# Ethernet.net
KiCad netlist of a schematic drawn in Altium Designer
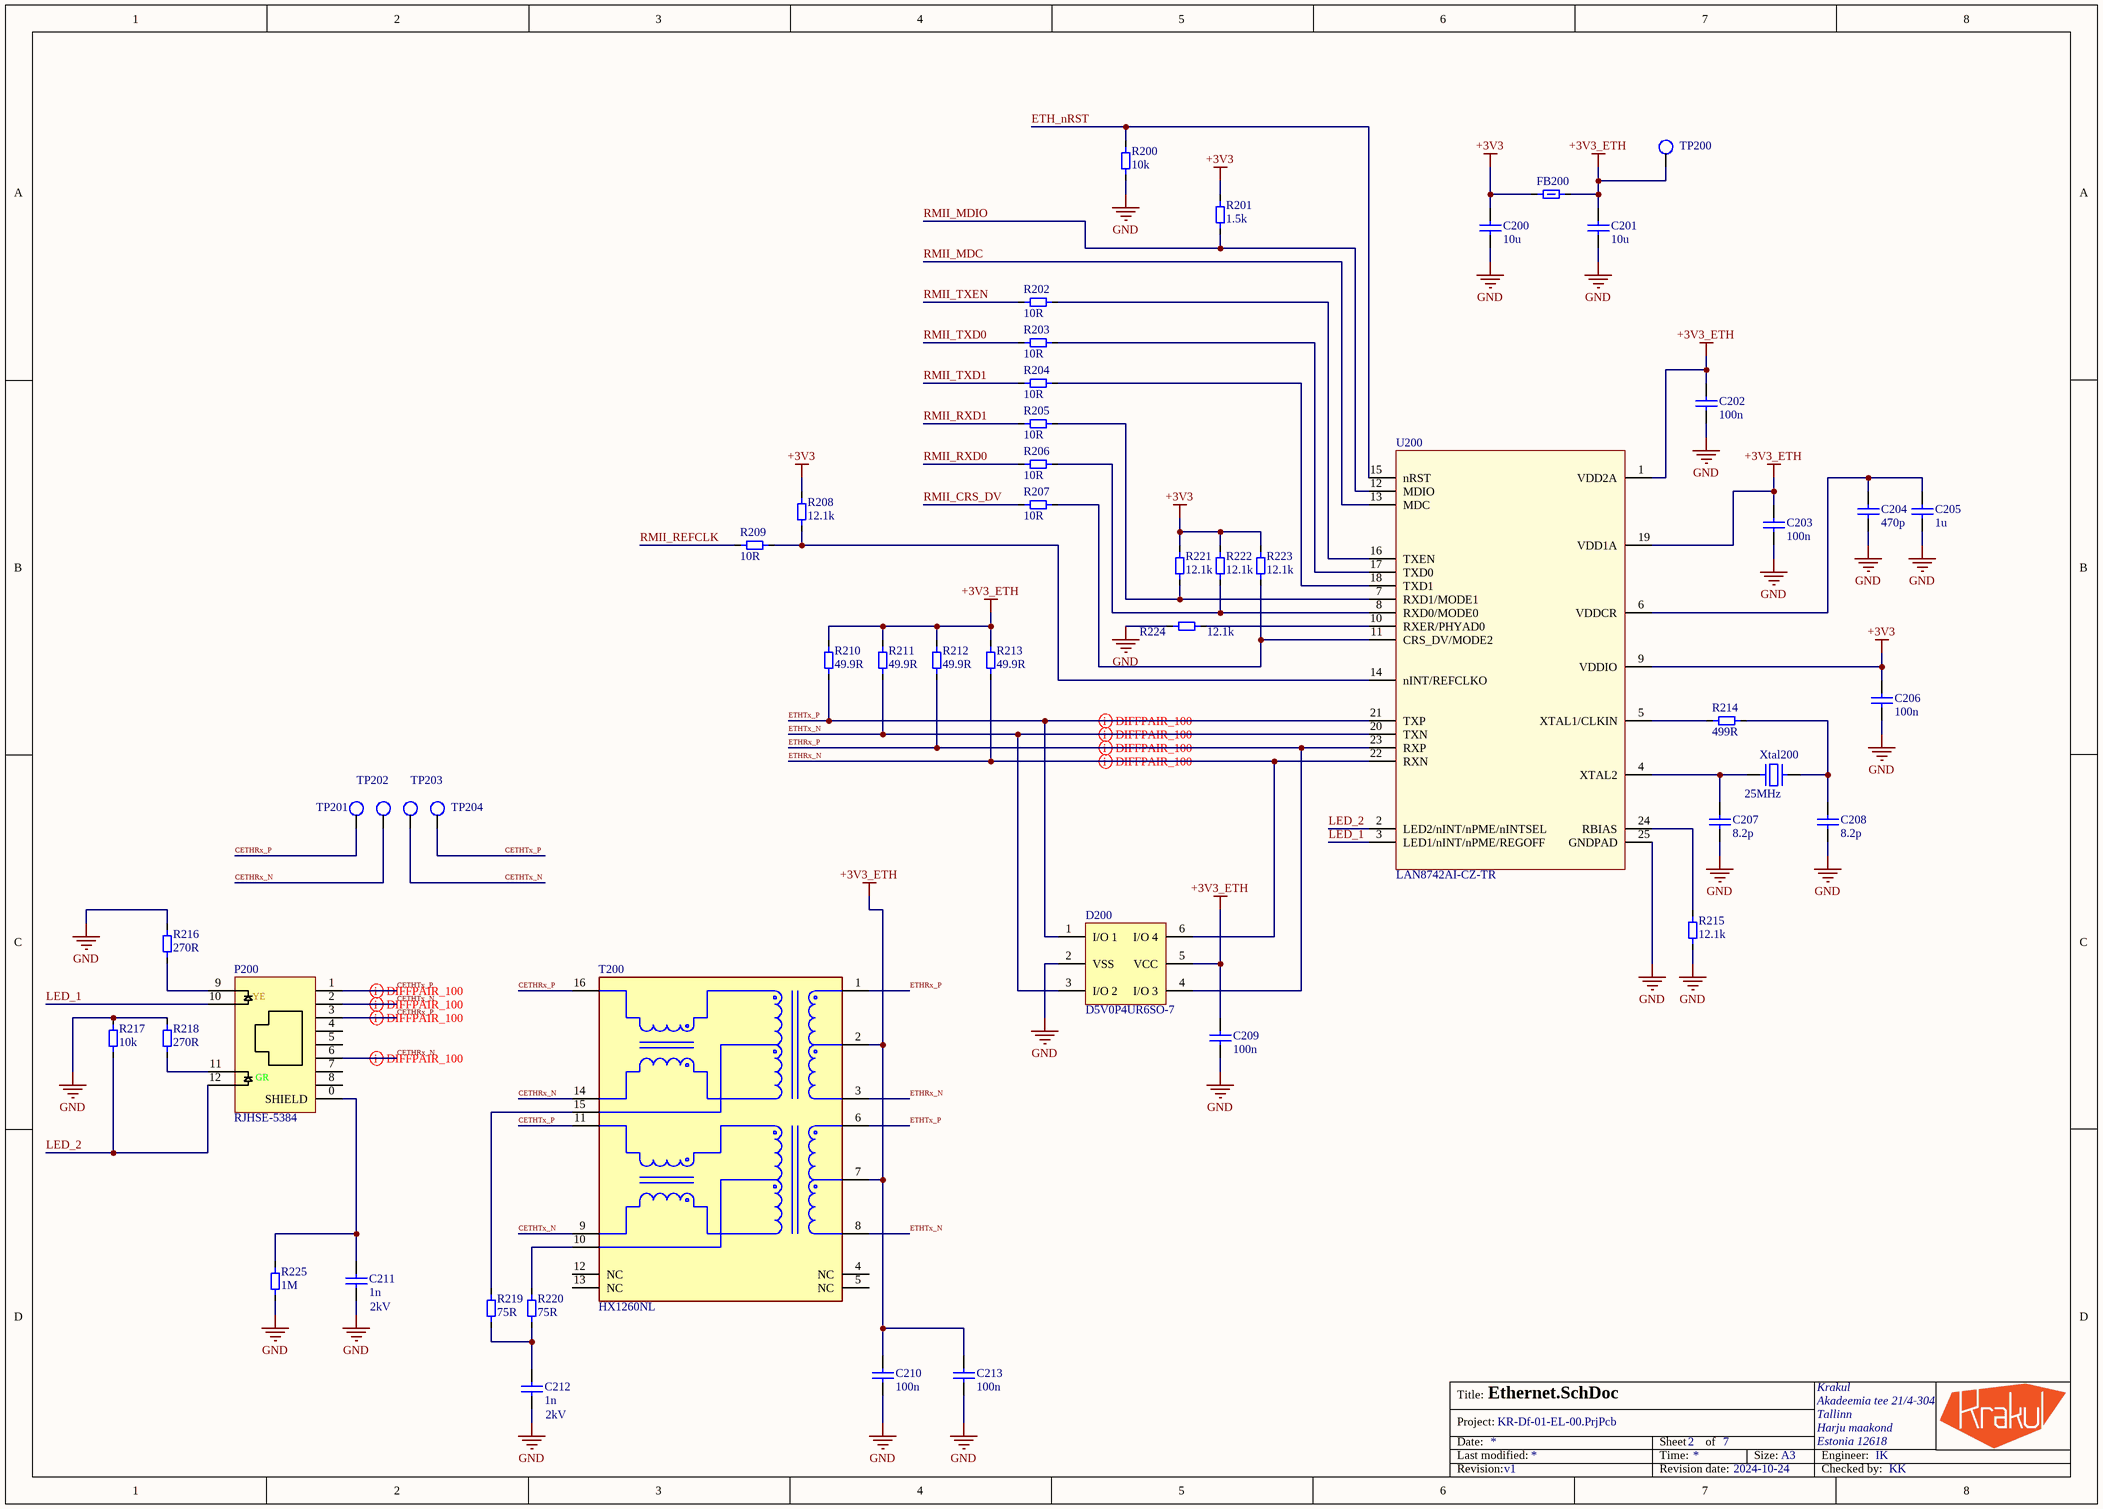
[diagram p0: Ethernet.SchDoc]

(export (version "E")
  (design (tool "Eeschema 10.0.6"))
  (components
    (comp (ref "C200")
      (value "10u")
      (footprint "MLCC_0603_M")
      (description "MLCC, 0603, 10u, 10%, 25V, X5R")
      (fields (field (name "VOLTAGE") "25V") (field (name "MANUFACTURER") "Any"))
      (libsource (lib "Krakul Vault") (part "CAPACITOR_NONPOL_IEC"))
    )
    (comp (ref "C201")
      (value "10u")
      (footprint "MLCC_0603_M")
      (description "MLCC, 0603, 10u, 10%, 25V, X5R")
      (fields (field (name "VOLTAGE") "25V") (field (name "MANUFACTURER") "Any"))
      (libsource (lib "Krakul Vault") (part "CAPACITOR_NONPOL_IEC"))
    )
    (comp (ref "C202")
      (value "100n")
      (footprint "MLCC_0402_M")
      (description "MLCC, 0402, 100n, 10%, 10V, X5R")
      (fields (field (name "TOLERANCE") "10%") (field (name "MANUFACTURER") "Any"))
      (libsource (lib "Krakul Vault") (part "CAPACITOR_NONPOL_IEC"))
    )
    (comp (ref "C203")
      (value "100n")
      (footprint "MLCC_0402_M")
      (description "MLCC, 0402, 100n, 10%, 10V, X5R")
      (fields (field (name "TOLERANCE") "10%") (field (name "MANUFACTURER") "Any"))
      (libsource (lib "Krakul Vault") (part "CAPACITOR_NONPOL_IEC"))
    )
    (comp (ref "C204")
      (value "470p")
      (footprint "MLCC_0402_M")
      (description "MLCC, 0402, 470p, 5%, 50V, C0G/NP0")
      (fields (field (name "MANUFACTURER") "Any") (field (name "TOLERANCE") "5%"))
      (libsource (lib "Krakul Vault") (part "CAPACITOR_NONPOL_IEC"))
    )
    (comp (ref "C205")
      (value "1u")
      (footprint "MLCC_0603_M")
      (description "MLCC, 0603, 1u, 10%, 10V, X7R")
      (fields (field (name "TOLERANCE") "10%") (field (name "MANUFACTURER") "Any"))
      (libsource (lib "Krakul Vault") (part "CAPACITOR_NONPOL_IEC"))
    )
    (comp (ref "C206")
      (value "100n")
      (footprint "MLCC_0402_M")
      (description "MLCC, 0402, 100n, 10%, 10V, X5R")
      (fields (field (name "TOLERANCE") "10%") (field (name "MANUFACTURER") "Any"))
      (libsource (lib "Krakul Vault") (part "CAPACITOR_NONPOL_IEC"))
    )
    (comp (ref "C207")
      (value "8.2p")
      (footprint "MLCC_0402_M")
      (description "MLCC, 0402, 8.2p, 5%, 50V, C0G/NP0")
      (fields (field (name "MANUFACTURER") "Any") (field (name "VOLTAGE") "50V"))
      (libsource (lib "Krakul Vault") (part "CAPACITOR_NONPOL_IEC"))
    )
    (comp (ref "C208")
      (value "8.2p")
      (footprint "MLCC_0402_M")
      (description "MLCC, 0402, 8.2p, 5%, 50V, C0G/NP0")
      (fields (field (name "MANUFACTURER") "Any") (field (name "VOLTAGE") "50V"))
      (libsource (lib "Krakul Vault") (part "CAPACITOR_NONPOL_IEC"))
    )
    (comp (ref "C209")
      (value "100n")
      (footprint "MLCC_0402_M")
      (description "MLCC, 0402, 100n, 10%, 10V, X5R")
      (fields (field (name "TOLERANCE") "10%") (field (name "MANUFACTURER") "Any"))
      (libsource (lib "Krakul Vault") (part "CAPACITOR_NONPOL_IEC"))
    )
    (comp (ref "C210")
      (value "100n")
      (footprint "MLCC_0402_M")
      (description "MLCC, 0402, 100n, 10%, 10V, X5R")
      (fields (field (name "TOLERANCE") "10%") (field (name "MANUFACTURER") "Any"))
      (libsource (lib "Krakul Vault") (part "CAPACITOR_NONPOL_IEC"))
    )
    (comp (ref "C211")
      (value "1n")
      (footprint "MLCC_1206_M")
      (description "MLCC, 1206, 1n, 10%, 2kV, X7R")
      (fields
        (field (name "VOLTAGE RATING (DC)") "2kV")
        (field (name "MANUFACTURER") "Any")
        (field (name "VOLTAGE") "2kV")
      )
      (libsource (lib "Krakul Vault") (part "CAPACITOR_NONPOL_IEC"))
    )
    (comp (ref "C212")
      (value "1n")
      (footprint "MLCC_1206_M")
      (description "MLCC, 1206, 1n, 10%, 2kV, X7R")
      (fields
        (field (name "VOLTAGE RATING (DC)") "2kV")
        (field (name "MANUFACTURER") "Any")
        (field (name "VOLTAGE") "2kV")
      )
      (libsource (lib "Krakul Vault") (part "CAPACITOR_NONPOL_IEC"))
    )
    (comp (ref "C213")
      (value "100n")
      (footprint "MLCC_0402_M")
      (description "MLCC, 0402, 100n, 10%, 10V, X5R")
      (fields (field (name "TOLERANCE") "10%") (field (name "MANUFACTURER") "Any"))
      (libsource (lib "Krakul Vault") (part "CAPACITOR_NONPOL_IEC"))
    )
    (comp (ref "D200")
      (value "D5V0P4UR6SO-7")
      (footprint "SOT26")
      (description "DIODES INC. - D5V0P4UR6SO-7 - ESD Protection Device, 1.2 V, SOT-26, 6 Pins, 3.6 V, 300 mW")
      (fields (field (name "MANUFACTURER") "Diodes Inc"))
      (libsource (lib "Krakul Vault") (part "D5V0P4UR6SO"))
    )
    (comp (ref "FB200")
      (value "BLM18RK601SN1D")
      (footprint "FP-BLM18-0_15-t0_8-IPC_B")
      (description "Ferrite Beads Multi-Layer 600Ohm 25% 100MHz 200mA 600mOhm DCR 0603 T/R")
      (fields (field (name "MANUFACTURER") "Murata"))
      (libsource (lib "Krakul Vault") (part "FERRITE"))
    )
    (comp (ref "P200")
      (value "RJHSE-5384")
      (footprint "RJHSE-5384")
      (description "CONN MOD JACK 8P8C R/A SHIELDED, LEFT GREEN, RIGHT YELLOW")
      (fields (field (name "MANUFACTURER") "Amphenol ICC"))
      (libsource (lib "Krakul Vault") (part "RJ45 w/ LED-s"))
    )
    (comp (ref "R200")
      (value "10k")
      (footprint "Resistor_0603_M")
      (description "Resistor, 0603, 10k, 1%, 1/10W")
      (fields (field (name "MANUFACTURER") "Any") (field (name "TOLERANCE") "1%"))
      (libsource (lib "Krakul Vault") (part "RESISTOR_GENERIC_IEC"))
    )
    (comp (ref "R201")
      (value "1.5k")
      (footprint "Resistor_0402_M")
      (description "Resistor, 0402, 1.5k, 1%, 1/16W")
      (fields (field (name "POWER") "62mW") (field (name "TOLERANCE") "1%"))
      (libsource (lib "Krakul Vault") (part "RESISTOR_GENERIC_IEC"))
    )
    (comp (ref "R202")
      (value "10R")
      (footprint "Resistor_0402_M")
      (description "Resistor, 0402, 10R, 1%, 1/16W")
      (fields (field (name "POWER") "62mW") (field (name "MANUFACTURER") "Any"))
      (libsource (lib "Krakul Vault") (part "RESISTOR_GENERIC_IEC"))
    )
    (comp (ref "R203")
      (value "10R")
      (footprint "Resistor_0402_M")
      (description "Resistor, 0402, 10R, 1%, 1/16W")
      (fields (field (name "POWER") "62mW") (field (name "MANUFACTURER") "Any"))
      (libsource (lib "Krakul Vault") (part "RESISTOR_GENERIC_IEC"))
    )
    (comp (ref "R204")
      (value "10R")
      (footprint "Resistor_0402_M")
      (description "Resistor, 0402, 10R, 1%, 1/16W")
      (fields (field (name "POWER") "62mW") (field (name "MANUFACTURER") "Any"))
      (libsource (lib "Krakul Vault") (part "RESISTOR_GENERIC_IEC"))
    )
    (comp (ref "R205")
      (value "10R")
      (footprint "Resistor_0402_M")
      (description "Resistor, 0402, 10R, 1%, 1/16W")
      (fields (field (name "POWER") "62mW") (field (name "MANUFACTURER") "Any"))
      (libsource (lib "Krakul Vault") (part "RESISTOR_GENERIC_IEC"))
    )
    (comp (ref "R206")
      (value "10R")
      (footprint "Resistor_0402_M")
      (description "Resistor, 0402, 10R, 1%, 1/16W")
      (fields (field (name "POWER") "62mW") (field (name "MANUFACTURER") "Any"))
      (libsource (lib "Krakul Vault") (part "RESISTOR_GENERIC_IEC"))
    )
    (comp (ref "R207")
      (value "10R")
      (footprint "Resistor_0402_M")
      (description "Resistor, 0402, 10R, 1%, 1/16W")
      (fields (field (name "POWER") "62mW") (field (name "MANUFACTURER") "Any"))
      (libsource (lib "Krakul Vault") (part "RESISTOR_GENERIC_IEC"))
    )
    (comp (ref "R208")
      (value "12.1k")
      (footprint "Resistor_0402_M")
      (description "Resistor, 0402, 12.1k, 1%, 1/16W")
      (fields (field (name "MANUFACTURER") "Any") (field (name "TOLERANCE") "1%"))
      (libsource (lib "Krakul Vault") (part "RESISTOR_GENERIC_IEC"))
    )
    (comp (ref "R209")
      (value "10R")
      (footprint "Resistor_0402_M")
      (description "Resistor, 0402, 10R, 1%, 1/16W")
      (fields (field (name "POWER") "62mW") (field (name "MANUFACTURER") "Any"))
      (libsource (lib "Krakul Vault") (part "RESISTOR_GENERIC_IEC"))
    )
    (comp (ref "R210")
      (value "49.9R")
      (footprint "Resistor_0402_M")
      (description "Resistor, 0402, 49.9R, 1%, 1/16W")
      (fields (field (name "MANUFACTURER") "Any") (field (name "POWER") "62mW"))
      (libsource (lib "Krakul Vault") (part "RESISTOR_GENERIC_IEC"))
    )
    (comp (ref "R211")
      (value "49.9R")
      (footprint "Resistor_0402_M")
      (description "Resistor, 0402, 49.9R, 1%, 1/16W")
      (fields (field (name "MANUFACTURER") "Any") (field (name "POWER") "62mW"))
      (libsource (lib "Krakul Vault") (part "RESISTOR_GENERIC_IEC"))
    )
    (comp (ref "R212")
      (value "49.9R")
      (footprint "Resistor_0402_M")
      (description "Resistor, 0402, 49.9R, 1%, 1/16W")
      (fields (field (name "MANUFACTURER") "Any") (field (name "POWER") "62mW"))
      (libsource (lib "Krakul Vault") (part "RESISTOR_GENERIC_IEC"))
    )
    (comp (ref "R213")
      (value "49.9R")
      (footprint "Resistor_0402_M")
      (description "Resistor, 0402, 49.9R, 1%, 1/16W")
      (fields (field (name "MANUFACTURER") "Any") (field (name "POWER") "62mW"))
      (libsource (lib "Krakul Vault") (part "RESISTOR_GENERIC_IEC"))
    )
    (comp (ref "R214")
      (value "499R")
      (footprint "Resistor_0402_M")
      (description "Resistor, 0402, 499R, 1%, 1/16W")
      (fields (field (name "POWER") "62mW") (field (name "TOLERANCE") "1%"))
      (libsource (lib "Krakul Vault") (part "RESISTOR_GENERIC_IEC"))
    )
    (comp (ref "R215")
      (value "12.1k")
      (footprint "Resistor_0402_M")
      (description "Resistor, 0402, 12.1k, 1%, 1/16W")
      (fields (field (name "MANUFACTURER") "Any") (field (name "TOLERANCE") "1%"))
      (libsource (lib "Krakul Vault") (part "RESISTOR_GENERIC_IEC"))
    )
    (comp (ref "R216")
      (value "270R")
      (footprint "Resistor_0402_M")
      (description "Resistor, 0402, 270R, 1%, 1/16W")
      (fields (field (name "POWER") "62mW") (field (name "TOLERANCE") "1%"))
      (libsource (lib "Krakul Vault") (part "RESISTOR_GENERIC_IEC"))
    )
    (comp (ref "R217")
      (value "10k")
      (footprint "Resistor_0603_M")
      (description "Resistor, 0603, 10k, 1%, 1/10W")
      (fields (field (name "MANUFACTURER") "Any") (field (name "TOLERANCE") "1%"))
      (libsource (lib "Krakul Vault") (part "RESISTOR_GENERIC_IEC"))
    )
    (comp (ref "R218")
      (value "270R")
      (footprint "Resistor_0402_M")
      (description "Resistor, 0402, 270R, 1%, 1/16W")
      (fields (field (name "POWER") "62mW") (field (name "TOLERANCE") "1%"))
      (libsource (lib "Krakul Vault") (part "RESISTOR_GENERIC_IEC"))
    )
    (comp (ref "R219")
      (value "75R")
      (footprint "Resistor_0603_M")
      (description "Resistor, 0603, 75R, 1%, 1/10W")
      (fields (field (name "MANUFACTURER") "Any") (field (name "POWER") "100mW"))
      (libsource (lib "Krakul Vault") (part "RESISTOR_GENERIC_IEC"))
    )
    (comp (ref "R220")
      (value "75R")
      (footprint "Resistor_0603_M")
      (description "Resistor, 0603, 75R, 1%, 1/10W")
      (fields (field (name "MANUFACTURER") "Any") (field (name "POWER") "100mW"))
      (libsource (lib "Krakul Vault") (part "RESISTOR_GENERIC_IEC"))
    )
    (comp (ref "R221")
      (value "12.1k")
      (footprint "Resistor_0402_M")
      (description "Resistor, 0402, 12.1k, 1%, 1/16W")
      (fields (field (name "MANUFACTURER") "Any") (field (name "TOLERANCE") "1%"))
      (libsource (lib "Krakul Vault") (part "RESISTOR_GENERIC_IEC"))
    )
    (comp (ref "R222")
      (value "12.1k")
      (footprint "Resistor_0402_M")
      (description "Resistor, 0402, 12.1k, 1%, 1/16W")
      (fields (field (name "MANUFACTURER") "Any") (field (name "TOLERANCE") "1%"))
      (libsource (lib "Krakul Vault") (part "RESISTOR_GENERIC_IEC"))
    )
    (comp (ref "R223")
      (value "12.1k")
      (footprint "Resistor_0402_M")
      (description "Resistor, 0402, 12.1k, 1%, 1/16W")
      (fields (field (name "MANUFACTURER") "Any") (field (name "TOLERANCE") "1%"))
      (libsource (lib "Krakul Vault") (part "RESISTOR_GENERIC_IEC"))
    )
    (comp (ref "R224")
      (value "12.1k")
      (footprint "Resistor_0402_M")
      (description "Resistor, 0402, 12.1k, 1%, 1/16W")
      (fields (field (name "MANUFACTURER") "Any") (field (name "TOLERANCE") "1%"))
      (libsource (lib "Krakul Vault") (part "RESISTOR_GENERIC_IEC"))
    )
    (comp (ref "R225")
      (value "1M")
      (footprint "Resistor_1206_M")
      (description "Resistor, 1206, 1M, 1%, 1/4W")
      (fields (field (name "MANUFACTURER") "Any"))
      (libsource (lib "Krakul Vault") (part "RESISTOR_GENERIC_IEC"))
    )
    (comp (ref "T200")
      (value "HX1260NL")
      (footprint "FP-H1102NL-MFG")
      (description "Telecom Transformer 1: 1 0.65Ohm Prim. DCR 0.65Ohm Sec. DCR 16 Terminal Gull Wing SMD")
      (fields (field (name "MANUFACTURER") "Pulse"))
      (libsource (lib "Krakul Vault") (part "93ec76be72fdc3c71da4a2bb75782a6"))
    )
    (comp (ref "TP200")
      (value "Testpoint 1mm")
      (footprint "Testpoint 1mm")
      (libsource (lib "Krakul Vault") (part "Testpoint"))
    )
    (comp (ref "TP201")
      (value "Testpoint 1mm")
      (footprint "Testpoint 1mm")
      (libsource (lib "Krakul Vault") (part "Testpoint"))
    )
    (comp (ref "TP202")
      (value "Testpoint 1mm")
      (footprint "Testpoint 1mm")
      (libsource (lib "Krakul Vault") (part "Testpoint"))
    )
    (comp (ref "TP203")
      (value "Testpoint 1mm")
      (footprint "Testpoint 1mm")
      (libsource (lib "Krakul Vault") (part "Testpoint"))
    )
    (comp (ref "TP204")
      (value "Testpoint 1mm")
      (footprint "Testpoint 1mm")
      (libsource (lib "Krakul Vault") (part "Testpoint"))
    )
    (comp (ref "U200")
      (value "LAN8742AI-CZ-TR")
      (footprint "24-VFQFN Exposed Pad based on LAN8742AI-CZ-TR")
      (description "Small Footprint RMII 10/100 Ethernet Transceiver with flexPWR Technology")
      (fields (field (name "MANUFACTURER") "Microchip Technology"))
      (libsource (lib "Krakul Vault") (part "LAN8742AI-CZ-TR"))
    )
    (comp (ref "Xtal200")
      (value "ECS-250-10-37B-CTN-TR")
      (footprint "4-SMD Crystal 2.00mm x 1.60mm")
      (description "25MHz ±10ppm Crystal 10pF 50 Ohms 4-SMD, No Lead")
      (fields (field (name "FREQUENCY") "25MHz") (field (name "MANUFACTURER") "ECS Inc."))
      (libsource (lib "Krakul Vault") (part "Crystal 4 pins (pins 2, 4 hidden)"))
    )
  )
  (nets
    (net (code "1") (name "+3V3") (class "Default")
      (node (ref "C200") (pin "2") (pinfunction "2_2") (pintype "passive"))
      (node (ref "C206") (pin "2") (pinfunction "2_2") (pintype "passive"))
      (node (ref "FB200") (pin "1") (pinfunction "1_1") (pintype "passive"))
      (node (ref "R201") (pin "2") (pinfunction "2_2") (pintype "passive"))
      (node (ref "R208") (pin "2") (pinfunction "2_2") (pintype "passive"))
      (node (ref "R221") (pin "2") (pinfunction "2_2") (pintype "passive"))
      (node (ref "R222") (pin "2") (pinfunction "2_2") (pintype "passive"))
      (node (ref "R223") (pin "2") (pinfunction "2_2") (pintype "passive"))
      (node (ref "U200") (pin "9") (pinfunction "VDDIO_9") (pintype "passive"))
    )
    (net (code "2") (name "+3V3_ETH") (class "Default")
      (node (ref "C201") (pin "2") (pinfunction "2_2") (pintype "passive"))
      (node (ref "C202") (pin "2") (pinfunction "2_2") (pintype "passive"))
      (node (ref "C203") (pin "2") (pinfunction "2_2") (pintype "passive"))
      (node (ref "C209") (pin "2") (pinfunction "2_2") (pintype "passive"))
      (node (ref "C210") (pin "2") (pinfunction "2_2") (pintype "passive"))
      (node (ref "C213") (pin "2") (pinfunction "2_2") (pintype "passive"))
      (node (ref "D200") (pin "5") (pinfunction "VCC_5") (pintype "passive"))
      (node (ref "FB200") (pin "2") (pinfunction "2_2") (pintype "passive"))
      (node (ref "R210") (pin "2") (pinfunction "2_2") (pintype "passive"))
      (node (ref "R211") (pin "2") (pinfunction "2_2") (pintype "passive"))
      (node (ref "R212") (pin "2") (pinfunction "2_2") (pintype "passive"))
      (node (ref "R213") (pin "2") (pinfunction "2_2") (pintype "passive"))
      (node (ref "T200") (pin "2") (pinfunction "CT_2") (pintype "passive"))
      (node (ref "T200") (pin "7") (pinfunction "CT_7") (pintype "passive"))
      (node (ref "TP200") (pin "1") (pinfunction "1_1") (pintype "passive"))
      (node (ref "U200") (pin "1") (pinfunction "VDD2A_1") (pintype "passive"))
      (node (ref "U200") (pin "19") (pinfunction "VDD1A_19") (pintype "passive"))
    )
    (net (code "3") (name "/CETHRx_N") (class "Default")
      (node (ref "P200") (pin "6") (pinfunction "6_6") (pintype "passive"))
      (node (ref "T200") (pin "14") (pinfunction "TX-_14") (pintype "passive"))
      (node (ref "TP202") (pin "1") (pinfunction "1_1") (pintype "passive"))
    )
    (net (code "4") (name "/CETHRx_P") (class "Default")
      (node (ref "P200") (pin "3") (pinfunction "3_3") (pintype "passive"))
      (node (ref "T200") (pin "16") (pinfunction "TX+_16") (pintype "passive"))
      (node (ref "TP201") (pin "1") (pinfunction "1_1") (pintype "passive"))
    )
    (net (code "5") (name "/CETHTx_N") (class "Default")
      (node (ref "P200") (pin "2") (pinfunction "2_2") (pintype "passive"))
      (node (ref "T200") (pin "9") (pinfunction "RX-_9") (pintype "passive"))
      (node (ref "TP203") (pin "1") (pinfunction "1_1") (pintype "passive"))
    )
    (net (code "6") (name "/CETHTx_P") (class "Default")
      (node (ref "P200") (pin "1") (pinfunction "1_1") (pintype "passive"))
      (node (ref "T200") (pin "11") (pinfunction "RX+_11") (pintype "passive"))
      (node (ref "TP204") (pin "1") (pinfunction "1_1") (pintype "passive"))
    )
    (net (code "7") (name "/ETHRx_N") (class "Default")
      (node (ref "D200") (pin "6") (pinfunction "I/O_4_6") (pintype "passive"))
      (node (ref "R213") (pin "1") (pinfunction "1_1") (pintype "passive"))
      (node (ref "T200") (pin "3") (pinfunction "TD-_3") (pintype "passive"))
      (node (ref "U200") (pin "22") (pinfunction "RXN_22") (pintype "passive"))
    )
    (net (code "8") (name "/ETHRx_P") (class "Default")
      (node (ref "D200") (pin "4") (pinfunction "I/O_3_4") (pintype "passive"))
      (node (ref "R212") (pin "1") (pinfunction "1_1") (pintype "passive"))
      (node (ref "T200") (pin "1") (pinfunction "TD+_1") (pintype "passive"))
      (node (ref "U200") (pin "23") (pinfunction "RXP_23") (pintype "passive"))
    )
    (net (code "9") (name "/ETHTx_N") (class "Default")
      (node (ref "D200") (pin "3") (pinfunction "I/O_2_3") (pintype "passive"))
      (node (ref "R211") (pin "1") (pinfunction "1_1") (pintype "passive"))
      (node (ref "T200") (pin "8") (pinfunction "RD-_8") (pintype "passive"))
      (node (ref "U200") (pin "20") (pinfunction "TXN_20") (pintype "passive"))
    )
    (net (code "10") (name "/ETHTx_P") (class "Default")
      (node (ref "D200") (pin "1") (pinfunction "I/O_1_1") (pintype "passive"))
      (node (ref "R210") (pin "1") (pinfunction "1_1") (pintype "passive"))
      (node (ref "T200") (pin "6") (pinfunction "RD+_6") (pintype "passive"))
      (node (ref "U200") (pin "21") (pinfunction "TXP_21") (pintype "passive"))
    )
    (net (code "11") (name "/ETH_nRST") (class "Default")
      (node (ref "R200") (pin "2") (pinfunction "2_2") (pintype "passive"))
      (node (ref "U200") (pin "15") (pinfunction "nRST_15") (pintype "passive"))
    )
    (net (code "12") (name "/LED_1") (class "Default")
      (node (ref "P200") (pin "10") (pinfunction "10_10") (pintype "passive"))
      (node (ref "U200") (pin "3") (pinfunction "LED1/nINT/nPME/REGOFF_3") (pintype "passive"))
    )
    (net (code "13") (name "/LED_2") (class "Default")
      (node (ref "P200") (pin "12") (pinfunction "12_12") (pintype "passive"))
      (node (ref "R217") (pin "1") (pinfunction "1_1") (pintype "passive"))
      (node (ref "U200") (pin "2") (pinfunction "LED2/nINT/nPME/nINTSEL_2") (pintype "passive"))
    )
    (net (code "14") (name "/RMII_CRS_DV") (class "Default")
      (node (ref "R207") (pin "1") (pinfunction "1_1") (pintype "passive"))
    )
    (net (code "15") (name "/RMII_MDC") (class "Default")
      (node (ref "U200") (pin "13") (pinfunction "MDC_13") (pintype "passive"))
    )
    (net (code "16") (name "/RMII_MDIO") (class "Default")
      (node (ref "R201") (pin "1") (pinfunction "1_1") (pintype "passive"))
      (node (ref "U200") (pin "12") (pinfunction "MDIO_12") (pintype "passive"))
    )
    (net (code "17") (name "/RMII_REFCLK") (class "Default")
      (node (ref "R209") (pin "1") (pinfunction "1_1") (pintype "passive"))
    )
    (net (code "18") (name "/RMII_RXD0") (class "Default")
      (node (ref "R206") (pin "1") (pinfunction "1_1") (pintype "passive"))
    )
    (net (code "19") (name "/RMII_RXD1") (class "Default")
      (node (ref "R205") (pin "1") (pinfunction "1_1") (pintype "passive"))
    )
    (net (code "20") (name "/RMII_TXD0") (class "Default")
      (node (ref "R203") (pin "1") (pinfunction "1_1") (pintype "passive"))
    )
    (net (code "21") (name "/RMII_TXD1") (class "Default")
      (node (ref "R204") (pin "1") (pinfunction "1_1") (pintype "passive"))
    )
    (net (code "22") (name "/RMII_TXEN") (class "Default")
      (node (ref "R202") (pin "1") (pinfunction "1_1") (pintype "passive"))
    )
    (net (code "23") (name "GND") (class "Default")
      (node (ref "C200") (pin "1") (pinfunction "1_1") (pintype "passive"))
      (node (ref "C201") (pin "1") (pinfunction "1_1") (pintype "passive"))
      (node (ref "C202") (pin "1") (pinfunction "1_1") (pintype "passive"))
      (node (ref "C203") (pin "1") (pinfunction "1_1") (pintype "passive"))
      (node (ref "C204") (pin "1") (pinfunction "1_1") (pintype "passive"))
      (node (ref "C205") (pin "1") (pinfunction "1_1") (pintype "passive"))
      (node (ref "C206") (pin "1") (pinfunction "1_1") (pintype "passive"))
      (node (ref "C207") (pin "1") (pinfunction "1_1") (pintype "passive"))
      (node (ref "C208") (pin "1") (pinfunction "1_1") (pintype "passive"))
      (node (ref "C209") (pin "1") (pinfunction "1_1") (pintype "passive"))
      (node (ref "C210") (pin "1") (pinfunction "1_1") (pintype "passive"))
      (node (ref "C211") (pin "2") (pinfunction "2_2") (pintype "passive"))
      (node (ref "C212") (pin "1") (pinfunction "1_1") (pintype "passive"))
      (node (ref "C213") (pin "1") (pinfunction "1_1") (pintype "passive"))
      (node (ref "D200") (pin "2") (pinfunction "VSS_2") (pintype "passive"))
      (node (ref "R200") (pin "1") (pinfunction "1_1") (pintype "passive"))
      (node (ref "R215") (pin "1") (pinfunction "1_1") (pintype "passive"))
      (node (ref "R216") (pin "2") (pinfunction "2_2") (pintype "passive"))
      (node (ref "R217") (pin "2") (pinfunction "2_2") (pintype "passive"))
      (node (ref "R218") (pin "2") (pinfunction "2_2") (pintype "passive"))
      (node (ref "R224") (pin "1") (pinfunction "1_1") (pintype "passive"))
      (node (ref "R225") (pin "1") (pinfunction "1_1") (pintype "passive"))
      (node (ref "U200") (pin "25") (pinfunction "GNDPAD_25") (pintype "passive"))
      (node (ref "Xtal200") (pin "2") (pinfunction "GND_2") (pintype "power_in"))
      (node (ref "Xtal200") (pin "4") (pinfunction "GND_4") (pintype "power_in"))
    )
    (net (code "24") (name "Net-(C208-Pad2)") (class "Default")
      (node (ref "C208") (pin "2") (pinfunction "2_2") (pintype "passive"))
      (node (ref "R214") (pin "2") (pinfunction "2_2") (pintype "passive"))
      (node (ref "Xtal200") (pin "3") (pinfunction "3_3") (pintype "passive"))
    )
    (net (code "25") (name "Net-(C212-Pad2)") (class "Default")
      (node (ref "C212") (pin "2") (pinfunction "2_2") (pintype "passive"))
      (node (ref "R219") (pin "1") (pinfunction "1_1") (pintype "passive"))
      (node (ref "R220") (pin "1") (pinfunction "1_1") (pintype "passive"))
    )
    (net (code "26") (name "Net-(P200-Pad9)") (class "Default")
      (node (ref "P200") (pin "9") (pinfunction "9_9") (pintype "passive"))
      (node (ref "R216") (pin "1") (pinfunction "1_1") (pintype "passive"))
    )
    (net (code "27") (name "Net-(P200-Pad11)") (class "Default")
      (node (ref "P200") (pin "11") (pinfunction "11_11") (pintype "passive"))
      (node (ref "R218") (pin "1") (pinfunction "1_1") (pintype "passive"))
    )
    (net (code "28") (name "Net-(P200-SHIELD)") (class "Default")
      (node (ref "C211") (pin "1") (pinfunction "1_1") (pintype "passive"))
      (node (ref "P200") (pin "0") (pinfunction "SHIELD_0") (pintype "passive"))
      (node (ref "R225") (pin "2") (pinfunction "2_2") (pintype "passive"))
    )
    (net (code "29") (name "Net-(R219-Pad2)") (class "Default")
      (node (ref "R219") (pin "2") (pinfunction "2_2") (pintype "passive"))
      (node (ref "T200") (pin "15") (pinfunction "NC_15") (pintype "passive"))
    )
    (net (code "30") (name "Net-(R220-Pad2)") (class "Default")
      (node (ref "R220") (pin "2") (pinfunction "2_2") (pintype "passive"))
      (node (ref "T200") (pin "10") (pinfunction "NC_10") (pintype "passive"))
    )
    (net (code "31") (name "Net-(U200-CRS_DV{slash}MODE2)") (class "Default")
      (node (ref "R207") (pin "2") (pinfunction "2_2") (pintype "passive"))
      (node (ref "R223") (pin "1") (pinfunction "1_1") (pintype "passive"))
      (node (ref "U200") (pin "11") (pinfunction "CRS_DV/MODE2_11") (pintype "passive"))
    )
    (net (code "32") (name "Net-(U200-RBIAS)") (class "Default")
      (node (ref "R215") (pin "2") (pinfunction "2_2") (pintype "passive"))
      (node (ref "U200") (pin "24") (pinfunction "RBIAS_24") (pintype "passive"))
    )
    (net (code "33") (name "Net-(U200-RXD0{slash}MODE0)") (class "Default")
      (node (ref "R206") (pin "2") (pinfunction "2_2") (pintype "passive"))
      (node (ref "R222") (pin "1") (pinfunction "1_1") (pintype "passive"))
      (node (ref "U200") (pin "8") (pinfunction "RXD0/MODE0_8") (pintype "passive"))
    )
    (net (code "34") (name "Net-(U200-RXD1{slash}MODE1)") (class "Default")
      (node (ref "R205") (pin "2") (pinfunction "2_2") (pintype "passive"))
      (node (ref "R221") (pin "1") (pinfunction "1_1") (pintype "passive"))
      (node (ref "U200") (pin "7") (pinfunction "RXD1/MODE1_7") (pintype "passive"))
    )
    (net (code "35") (name "Net-(U200-RXER{slash}PHYAD0)") (class "Default")
      (node (ref "R224") (pin "2") (pinfunction "2_2") (pintype "passive"))
      (node (ref "U200") (pin "10") (pinfunction "RXER/PHYAD0_10") (pintype "passive"))
    )
    (net (code "36") (name "Net-(U200-TXD0)") (class "Default")
      (node (ref "R203") (pin "2") (pinfunction "2_2") (pintype "passive"))
      (node (ref "U200") (pin "17") (pinfunction "TXD0_17") (pintype "passive"))
    )
    (net (code "37") (name "Net-(U200-TXD1)") (class "Default")
      (node (ref "R204") (pin "2") (pinfunction "2_2") (pintype "passive"))
      (node (ref "U200") (pin "18") (pinfunction "TXD1_18") (pintype "passive"))
    )
    (net (code "38") (name "Net-(U200-TXEN)") (class "Default")
      (node (ref "R202") (pin "2") (pinfunction "2_2") (pintype "passive"))
      (node (ref "U200") (pin "16") (pinfunction "TXEN_16") (pintype "passive"))
    )
    (net (code "39") (name "Net-(U200-VDDCR)") (class "Default")
      (node (ref "C204") (pin "2") (pinfunction "2_2") (pintype "passive"))
      (node (ref "C205") (pin "2") (pinfunction "2_2") (pintype "passive"))
      (node (ref "U200") (pin "6") (pinfunction "VDDCR_6") (pintype "passive"))
    )
    (net (code "40") (name "Net-(U200-XTAL1{slash}CLKIN)") (class "Default")
      (node (ref "R214") (pin "1") (pinfunction "1_1") (pintype "passive"))
      (node (ref "U200") (pin "5") (pinfunction "XTAL1/CLKIN_5") (pintype "passive"))
    )
    (net (code "41") (name "Net-(U200-XTAL2)") (class "Default")
      (node (ref "C207") (pin "2") (pinfunction "2_2") (pintype "passive"))
      (node (ref "U200") (pin "4") (pinfunction "XTAL2_4") (pintype "passive"))
      (node (ref "Xtal200") (pin "1") (pinfunction "1_1") (pintype "passive"))
    )
    (net (code "42") (name "Net-(U200-nINT{slash}REFCLKO)") (class "Default")
      (node (ref "R208") (pin "1") (pinfunction "1_1") (pintype "passive"))
      (node (ref "R209") (pin "2") (pinfunction "2_2") (pintype "passive"))
      (node (ref "U200") (pin "14") (pinfunction "nINT/REFCLKO_14") (pintype "passive"))
    )
    (net (code "43") (name "unconnected-(P200-Pad4)") (class "Default")
      (node (ref "P200") (pin "4") (pinfunction "4_4") (pintype "passive"))
    )
    (net (code "44") (name "unconnected-(P200-Pad5)") (class "Default")
      (node (ref "P200") (pin "5") (pinfunction "5_5") (pintype "passive"))
    )
    (net (code "45") (name "unconnected-(P200-Pad7)") (class "Default")
      (node (ref "P200") (pin "7") (pinfunction "7_7") (pintype "passive"))
    )
    (net (code "46") (name "unconnected-(P200-Pad8)") (class "Default")
      (node (ref "P200") (pin "8") (pinfunction "8_8") (pintype "passive"))
    )
    (net (code "47") (name "unconnected-(T200-NC-Pad4)") (class "Default")
      (node (ref "T200") (pin "4") (pinfunction "NC_4") (pintype "passive"))
    )
    (net (code "48") (name "unconnected-(T200-NC-Pad5)") (class "Default")
      (node (ref "T200") (pin "5") (pinfunction "NC_5") (pintype "passive"))
    )
    (net (code "49") (name "unconnected-(T200-NC-Pad12)") (class "Default")
      (node (ref "T200") (pin "12") (pinfunction "NC_12") (pintype "passive"))
    )
    (net (code "50") (name "unconnected-(T200-NC-Pad13)") (class "Default")
      (node (ref "T200") (pin "13") (pinfunction "NC_13") (pintype "passive"))
    )
  )
)
